# MCU.net
KiCad netlist of a schematic drawn in Altium Designer
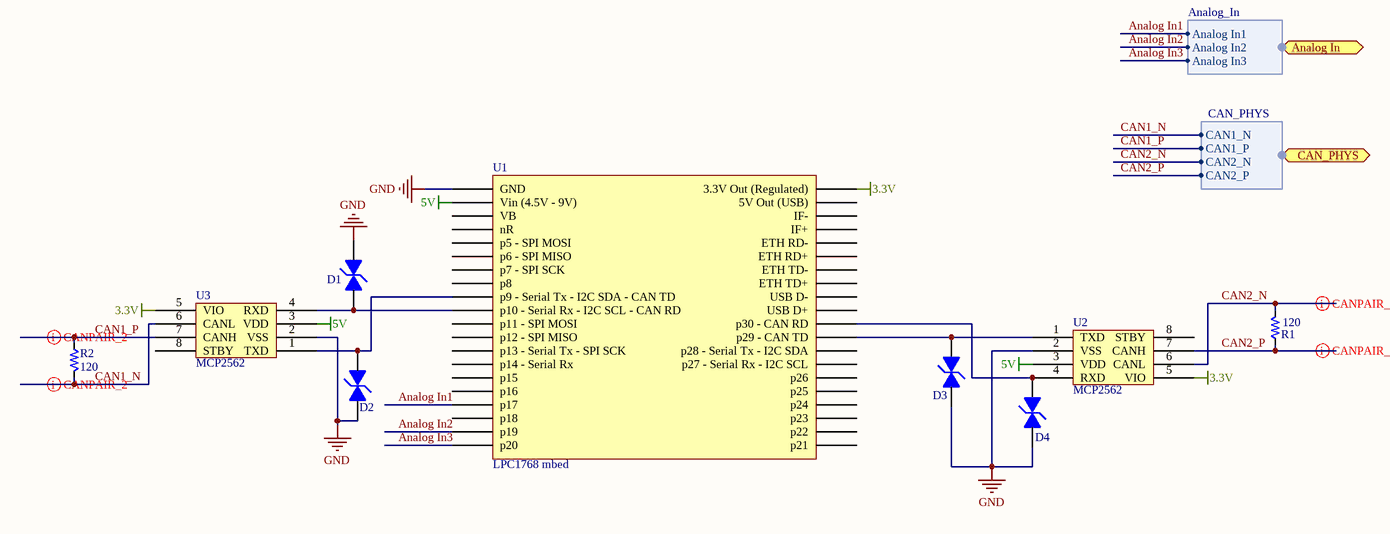
[diagram p0: MCU.SchDoc]

(export (version "E")
  (design (tool "Eeschema 10.0.6"))
  (components
    (comp (ref "D1")
      (value "TVS Diode")
      (footprint "TVS Diode")
      (fields (field (name "MANUFACTURER") "Bourns"))
      (libsource (lib "TVS Diode") (part "TVS Diode"))
    )
    (comp (ref "D2")
      (value "TVS Diode")
      (footprint "TVS Diode")
      (fields (field (name "MANUFACTURER") "Bourns"))
      (libsource (lib "TVS Diode") (part "TVS Diode"))
    )
    (comp (ref "D3")
      (value "TVS Diode")
      (footprint "TVS Diode")
      (fields (field (name "MANUFACTURER") "Bourns"))
      (libsource (lib "TVS Diode") (part "TVS Diode"))
    )
    (comp (ref "D4")
      (value "TVS Diode")
      (footprint "TVS Diode")
      (fields (field (name "MANUFACTURER") "Bourns"))
      (libsource (lib "TVS Diode") (part "TVS Diode"))
    )
    (comp (ref "R1")
      (value "120")
      (footprint "PCB_GENERIC_SMD_0603")
      (description "120 Ohms")
      (libsource (lib "SCH_GENERIC_RESISTOR_0603") (part "SCH_GENERIC_RESISTOR_0603"))
    )
    (comp (ref "R2")
      (value "120")
      (footprint "PCB_GENERIC_SMD_0603")
      (description "120 Ohms")
      (libsource (lib "SCH_GENERIC_RESISTOR_0603") (part "SCH_GENERIC_RESISTOR_0603"))
    )
    (comp (ref "U1")
      (value "LPC1768 mbed")
      (footprint "LPC 1768 mbed Layout")
      (libsource (lib "LPC1768_mbed_SCH") (part "LPC1768 mbed"))
    )
    (comp (ref "U2") (value "MCP2562") (footprint "MCP2562") (libsource (lib "MCP2562_SCH") (part "MCP2562")))
    (comp (ref "U3") (value "MCP2562") (footprint "MCP2562") (libsource (lib "") (part "MCP2562_1")))
  )
  (nets
    (net (code "3") (name "/Analog In1") (class "Default")
      (node (ref "U1") (pin "17") (pinfunction "p17_17") (pintype "passive"))
    )
    (net (code "4") (name "/Analog In2") (class "Default")
      (node (ref "U1") (pin "19") (pinfunction "p19_19") (pintype "passive"))
    )
    (net (code "5") (name "/Analog In3") (class "Default")
      (node (ref "U1") (pin "20") (pinfunction "p20_20") (pintype "passive"))
    )
    (net (code "6") (name "/CAN1_N") (class "Default")
      (node (ref "R2") (pin "2") (pinfunction "2_2") (pintype "passive"))
      (node (ref "U3") (pin "6") (pinfunction "CANL_6") (pintype "passive"))
    )
    (net (code "7") (name "/CAN1_P") (class "Default")
      (node (ref "R2") (pin "1") (pinfunction "1_1") (pintype "passive"))
      (node (ref "U3") (pin "7") (pinfunction "CANH_7") (pintype "passive"))
    )
    (net (code "8") (name "/CAN2_N") (class "Default")
      (node (ref "R1") (pin "2") (pinfunction "2_2") (pintype "passive"))
      (node (ref "U2") (pin "6") (pinfunction "CANL_6") (pintype "passive"))
    )
    (net (code "9") (name "/CAN2_P") (class "Default")
      (node (ref "R1") (pin "1") (pinfunction "1_1") (pintype "passive"))
      (node (ref "U2") (pin "7") (pinfunction "CANH_7") (pintype "passive"))
    )
    (net (code "12") (name "3.3V") (class "Default")
      (node (ref "U1") (pin "40") (pinfunction "3.3V_Out_(Regulated)_40") (pintype "passive"))
      (node (ref "U2") (pin "5") (pinfunction "VIO_5") (pintype "passive"))
      (node (ref "U3") (pin "5") (pinfunction "VIO_5") (pintype "passive"))
    )
    (net (code "13") (name "5V") (class "Default")
      (node (ref "U1") (pin "2") (pinfunction "Vin_(4.5V_-_9V)_2") (pintype "passive"))
      (node (ref "U2") (pin "3") (pinfunction "VDD_3") (pintype "passive"))
      (node (ref "U3") (pin "3") (pinfunction "VDD_3") (pintype "passive"))
    )
    (net (code "14") (name "GND") (class "Default")
      (node (ref "D1") (pin "2") (pintype "passive"))
      (node (ref "D2") (pin "2") (pintype "passive"))
      (node (ref "D3") (pin "1") (pintype "passive"))
      (node (ref "D4") (pin "1") (pintype "passive"))
      (node (ref "U1") (pin "1") (pinfunction "GND_1") (pintype "passive"))
      (node (ref "U2") (pin "2") (pinfunction "VSS_2") (pintype "passive"))
      (node (ref "U3") (pin "2") (pinfunction "VSS_2") (pintype "passive"))
    )
    (net (code "15") (name "Net-(U1-p9_-_Serial_Tx_-_I2C_SDA_-_CAN_TD)") (class "Default")
      (node (ref "D2") (pin "1") (pintype "passive"))
      (node (ref "U1") (pin "9") (pinfunction "p9_-_Serial_Tx_-_I2C_SDA_-_CAN_TD_9") (pintype "passive"))
      (node (ref "U3") (pin "1") (pinfunction "TXD_1") (pintype "passive"))
    )
    (net (code "16") (name "Net-(U1-p10_-_Serial_Rx_-_I2C_SCL_-_CAN_RD)") (class "Default")
      (node (ref "D1") (pin "1") (pintype "passive"))
      (node (ref "U1") (pin "10") (pinfunction "p10_-_Serial_Rx_-_I2C_SCL_-_CAN_RD_10") (pintype "passive"))
      (node (ref "U3") (pin "4") (pinfunction "RXD_4") (pintype "passive"))
    )
    (net (code "17") (name "Net-(U1-p29_-_CAN_TD)") (class "Default")
      (node (ref "D3") (pin "2") (pintype "passive"))
      (node (ref "U1") (pin "29") (pinfunction "p29_-_CAN_TD_29") (pintype "passive"))
      (node (ref "U2") (pin "1") (pinfunction "TXD_1") (pintype "passive"))
    )
    (net (code "18") (name "Net-(U1-p30_-_CAN_RD)") (class "Default")
      (node (ref "D4") (pin "2") (pintype "passive"))
      (node (ref "U1") (pin "30") (pinfunction "p30_-_CAN_RD_30") (pintype "passive"))
      (node (ref "U2") (pin "4") (pinfunction "RXD_4") (pintype "passive"))
    )
    (net (code "19") (name "unconnected-(U1-5V_Out_(USB)-Pad39)") (class "Default")
      (node (ref "U1") (pin "39") (pinfunction "5V_Out_(USB)_39") (pintype "passive"))
    )
    (net (code "20") (name "unconnected-(U1-ETH_RD+-Pad35)") (class "Default")
      (node (ref "U1") (pin "35") (pinfunction "ETH_RD+_35") (pintype "passive"))
    )
    (net (code "21") (name "unconnected-(U1-ETH_RD--Pad36)") (class "Default")
      (node (ref "U1") (pin "36") (pinfunction "ETH_RD-_36") (pintype "passive"))
    )
    (net (code "22") (name "unconnected-(U1-ETH_TD+-Pad33)") (class "Default")
      (node (ref "U1") (pin "33") (pinfunction "ETH_TD+_33") (pintype "passive"))
    )
    (net (code "23") (name "unconnected-(U1-ETH_TD--Pad34)") (class "Default")
      (node (ref "U1") (pin "34") (pinfunction "ETH_TD-_34") (pintype "passive"))
    )
    (net (code "24") (name "unconnected-(U1-IF+-Pad37)") (class "Default")
      (node (ref "U1") (pin "37") (pinfunction "IF+_37") (pintype "passive"))
    )
    (net (code "25") (name "unconnected-(U1-IF--Pad38)") (class "Default")
      (node (ref "U1") (pin "38") (pinfunction "IF-_38") (pintype "passive"))
    )
    (net (code "26") (name "unconnected-(U1-USB_D+-Pad31)") (class "Default")
      (node (ref "U1") (pin "31") (pinfunction "USB_D+_31") (pintype "passive"))
    )
    (net (code "27") (name "unconnected-(U1-USB_D--Pad32)") (class "Default")
      (node (ref "U1") (pin "32") (pinfunction "USB_D-_32") (pintype "passive"))
    )
    (net (code "28") (name "unconnected-(U1-VB-Pad3)") (class "Default")
      (node (ref "U1") (pin "3") (pinfunction "VB_3") (pintype "passive"))
    )
    (net (code "29") (name "unconnected-(U1-nR-Pad4)") (class "Default")
      (node (ref "U1") (pin "4") (pinfunction "nR_4") (pintype "passive"))
    )
    (net (code "30") (name "unconnected-(U1-p5_-_SPI_MOSI-Pad5)") (class "Default")
      (node (ref "U1") (pin "5") (pinfunction "p5_-_SPI_MOSI_5") (pintype "passive"))
    )
    (net (code "31") (name "unconnected-(U1-p6_-_SPI_MISO-Pad6)") (class "Default")
      (node (ref "U1") (pin "6") (pinfunction "p6_-_SPI_MISO_6") (pintype "passive"))
    )
    (net (code "32") (name "unconnected-(U1-p7_-_SPI_SCK-Pad7)") (class "Default")
      (node (ref "U1") (pin "7") (pinfunction "p7_-_SPI_SCK_7") (pintype "passive"))
    )
    (net (code "33") (name "unconnected-(U1-p8-Pad8)") (class "Default")
      (node (ref "U1") (pin "8") (pinfunction "p8_8") (pintype "passive"))
    )
    (net (code "34") (name "unconnected-(U1-p11_-_SPI_MOSI-Pad11)") (class "Default")
      (node (ref "U1") (pin "11") (pinfunction "p11_-_SPI_MOSI_11") (pintype "passive"))
    )
    (net (code "35") (name "unconnected-(U1-p12_-_SPI_MISO-Pad12)") (class "Default")
      (node (ref "U1") (pin "12") (pinfunction "p12_-_SPI_MISO_12") (pintype "passive"))
    )
    (net (code "36") (name "unconnected-(U1-p13_-_Serial_Tx_-_SPI_SCK-Pad13)") (class "Default")
      (node (ref "U1") (pin "13") (pinfunction "p13_-_Serial_Tx_-_SPI_SCK_13") (pintype "passive"))
    )
    (net (code "37") (name "unconnected-(U1-p14_-_Serial_Rx-Pad14)") (class "Default")
      (node (ref "U1") (pin "14") (pinfunction "p14_-_Serial_Rx_14") (pintype "passive"))
    )
    (net (code "38") (name "unconnected-(U1-p15-Pad15)") (class "Default")
      (node (ref "U1") (pin "15") (pinfunction "p15_15") (pintype "passive"))
    )
    (net (code "39") (name "unconnected-(U1-p16-Pad16)") (class "Default")
      (node (ref "U1") (pin "16") (pinfunction "p16_16") (pintype "passive"))
    )
    (net (code "40") (name "unconnected-(U1-p18-Pad18)") (class "Default")
      (node (ref "U1") (pin "18") (pinfunction "p18_18") (pintype "passive"))
    )
    (net (code "41") (name "unconnected-(U1-p21-Pad21)") (class "Default")
      (node (ref "U1") (pin "21") (pinfunction "p21_21") (pintype "passive"))
    )
    (net (code "42") (name "unconnected-(U1-p22-Pad22)") (class "Default")
      (node (ref "U1") (pin "22") (pinfunction "p22_22") (pintype "passive"))
    )
    (net (code "43") (name "unconnected-(U1-p23-Pad23)") (class "Default")
      (node (ref "U1") (pin "23") (pinfunction "p23_23") (pintype "passive"))
    )
    (net (code "44") (name "unconnected-(U1-p24-Pad24)") (class "Default")
      (node (ref "U1") (pin "24") (pinfunction "p24_24") (pintype "passive"))
    )
    (net (code "45") (name "unconnected-(U1-p25-Pad25)") (class "Default")
      (node (ref "U1") (pin "25") (pinfunction "p25_25") (pintype "passive"))
    )
    (net (code "46") (name "unconnected-(U1-p26-Pad26)") (class "Default")
      (node (ref "U1") (pin "26") (pinfunction "p26_26") (pintype "passive"))
    )
    (net (code "47") (name "unconnected-(U1-p27_-_Serial_Rx_-_I2C_SCL-Pad27)") (class "Default")
      (node (ref "U1") (pin "27") (pinfunction "p27_-_Serial_Rx_-_I2C_SCL_27") (pintype "passive"))
    )
    (net (code "48") (name "unconnected-(U1-p28_-_Serial_Tx_-_I2C_SDA-Pad28)") (class "Default")
      (node (ref "U1") (pin "28") (pinfunction "p28_-_Serial_Tx_-_I2C_SDA_28") (pintype "passive"))
    )
    (net (code "49") (name "unconnected-(U2-STBY-Pad8)") (class "Default")
      (node (ref "U2") (pin "8") (pinfunction "STBY_8") (pintype "passive"))
    )
    (net (code "50") (name "unconnected-(U3-STBY-Pad8)") (class "Default")
      (node (ref "U3") (pin "8") (pinfunction "STBY_8") (pintype "passive"))
    )
  )
)
